# SRC01.net
KiCad netlist of a schematic drawn in EAGLE
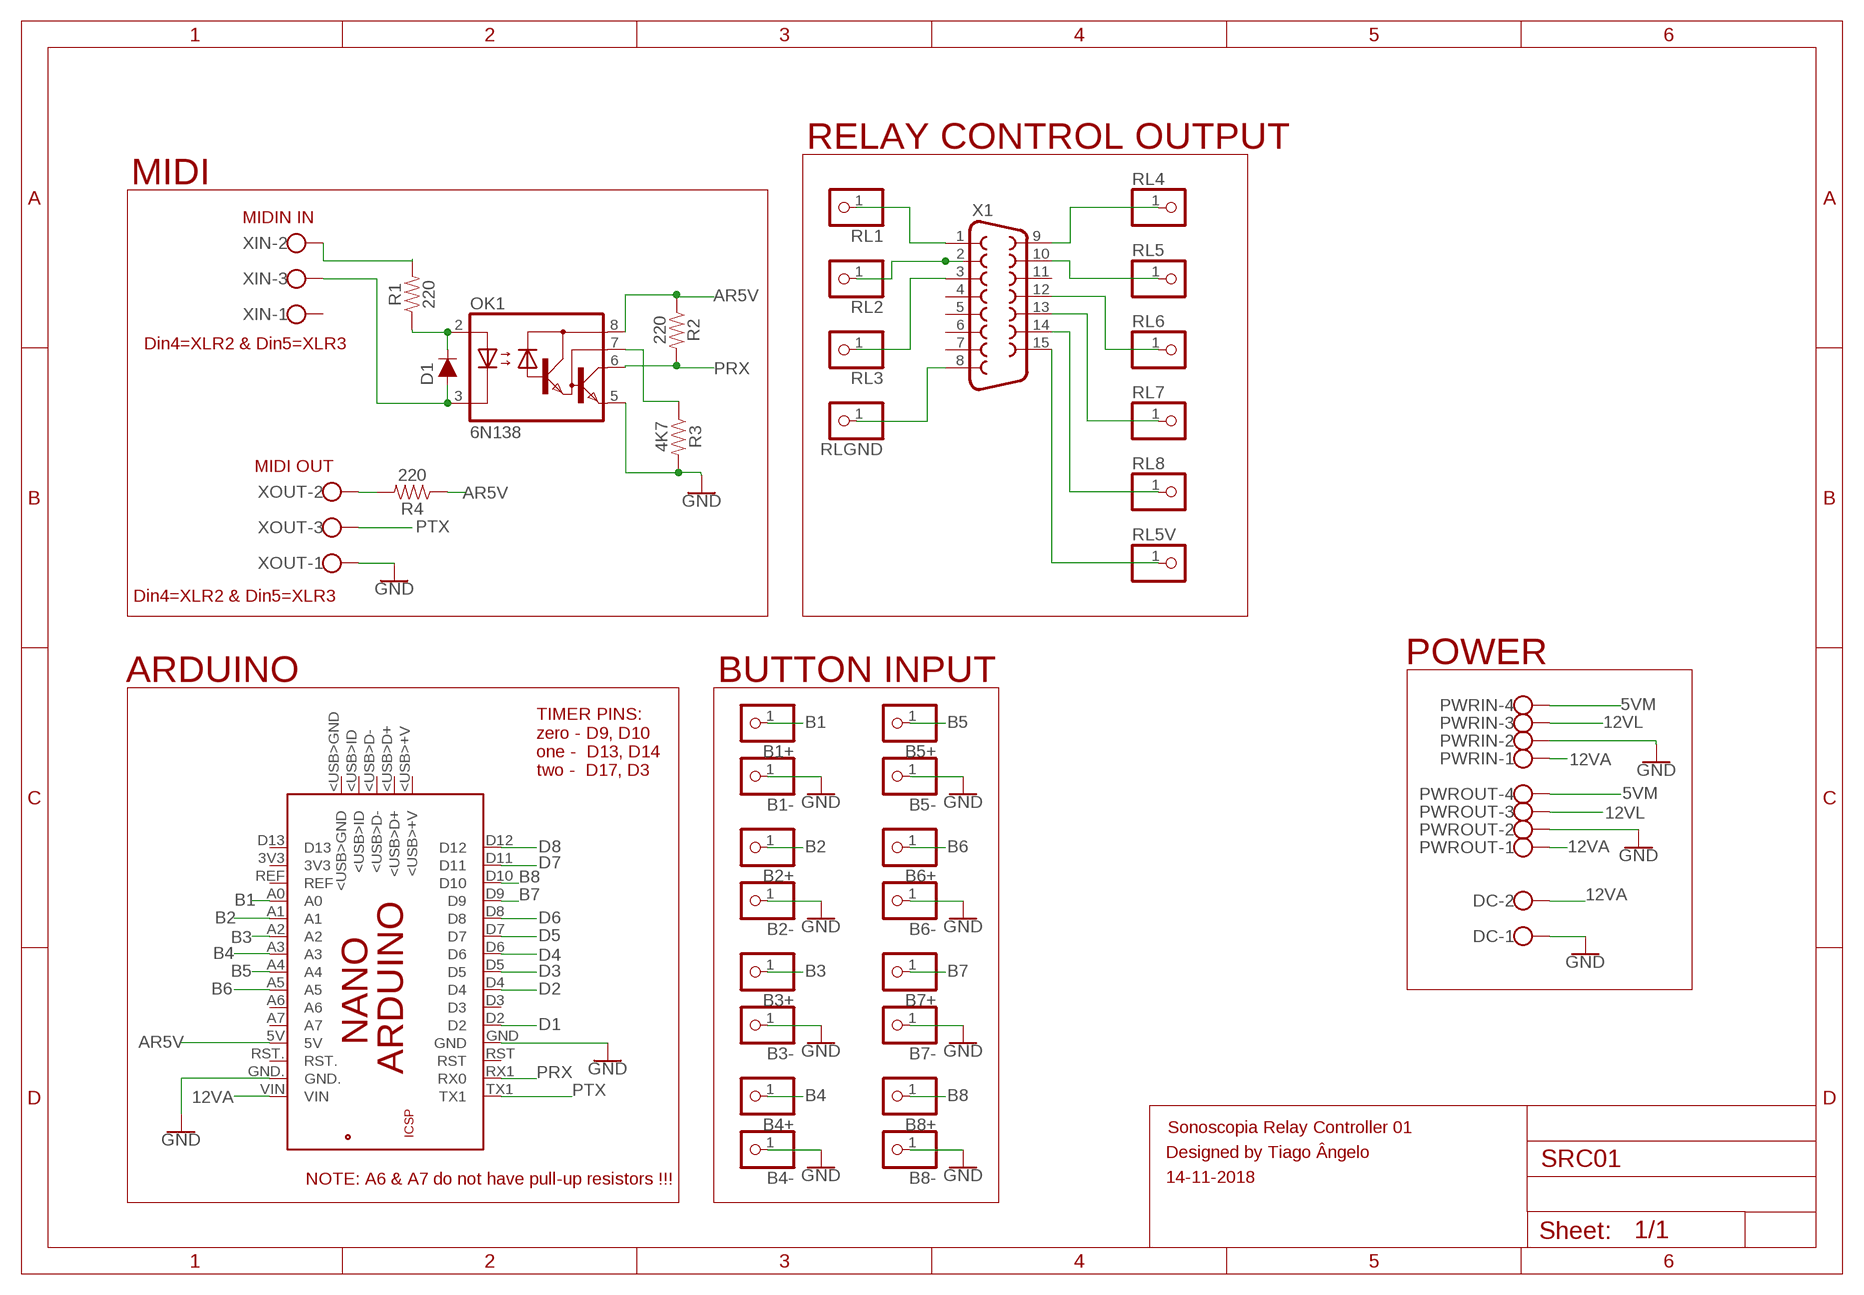
[diagram p0: schematic, sheet 1]

(export (version "E")
  (design (tool "Eeschema 10.0.6"))
  (components
    (comp (ref "B1+")
      (value "PINHD-1X1")
      (footprint "eagle-import:1X01")
      (libsource (lib "eagle-import") (part "PINHD-1X1"))
    )
    (comp (ref "B1-")
      (value "PINHD-1X1")
      (footprint "eagle-import:1X01")
      (libsource (lib "eagle-import") (part "PINHD-1X1"))
    )
    (comp (ref "B2+")
      (value "PINHD-1X1")
      (footprint "eagle-import:1X01")
      (libsource (lib "eagle-import") (part "PINHD-1X1"))
    )
    (comp (ref "B2-")
      (value "PINHD-1X1")
      (footprint "eagle-import:1X01")
      (libsource (lib "eagle-import") (part "PINHD-1X1"))
    )
    (comp (ref "B3+")
      (value "PINHD-1X1")
      (footprint "eagle-import:1X01")
      (libsource (lib "eagle-import") (part "PINHD-1X1"))
    )
    (comp (ref "B3-")
      (value "PINHD-1X1")
      (footprint "eagle-import:1X01")
      (libsource (lib "eagle-import") (part "PINHD-1X1"))
    )
    (comp (ref "B4+")
      (value "PINHD-1X1")
      (footprint "eagle-import:1X01")
      (libsource (lib "eagle-import") (part "PINHD-1X1"))
    )
    (comp (ref "B4-")
      (value "PINHD-1X1")
      (footprint "eagle-import:1X01")
      (libsource (lib "eagle-import") (part "PINHD-1X1"))
    )
    (comp (ref "B5+")
      (value "PINHD-1X1")
      (footprint "eagle-import:1X01")
      (libsource (lib "eagle-import") (part "PINHD-1X1"))
    )
    (comp (ref "B5-")
      (value "PINHD-1X1")
      (footprint "eagle-import:1X01")
      (libsource (lib "eagle-import") (part "PINHD-1X1"))
    )
    (comp (ref "B6+")
      (value "PINHD-1X1")
      (footprint "eagle-import:1X01")
      (libsource (lib "eagle-import") (part "PINHD-1X1"))
    )
    (comp (ref "B6-")
      (value "PINHD-1X1")
      (footprint "eagle-import:1X01")
      (libsource (lib "eagle-import") (part "PINHD-1X1"))
    )
    (comp (ref "B7+")
      (value "PINHD-1X1")
      (footprint "eagle-import:1X01")
      (libsource (lib "eagle-import") (part "PINHD-1X1"))
    )
    (comp (ref "B7-")
      (value "PINHD-1X1")
      (footprint "eagle-import:1X01")
      (libsource (lib "eagle-import") (part "PINHD-1X1"))
    )
    (comp (ref "B8+")
      (value "PINHD-1X1")
      (footprint "eagle-import:1X01")
      (libsource (lib "eagle-import") (part "PINHD-1X1"))
    )
    (comp (ref "B8-")
      (value "PINHD-1X1")
      (footprint "eagle-import:1X01")
      (libsource (lib "eagle-import") (part "PINHD-1X1"))
    )
    (comp (ref "D1")
      (value "200mA/100V/1V")
      (footprint "eagle-import:DIODE-1N4148")
      (libsource (lib "eagle-import") (part "DIODE-1N4148"))
    )
    (comp (ref "DC")
      (value "W237-102")
      (footprint "eagle-import:W237-102")
      (fields (field (name "MPN") "237-102"))
      (libsource (lib "eagle-import") (part "W237-102"))
    )
    (comp (ref "OK1")
      (value "6N138")
      (footprint "eagle-import:DIL08")
      (fields (field (name "MF") "VISHAY/TELEFUNKEN"))
      (libsource (lib "eagle-import") (part "6N138"))
    )
    (comp (ref "PCB1")
      (value "ARDUINO_NANO")
      (footprint "eagle-import:ARDUINO_NANO")
      (libsource (lib "eagle-import") (part "ARDUINO_NANO"))
    )
    (comp (ref "PWRIN")
      (value "W237-4")
      (footprint "eagle-import:W237-4")
      (libsource (lib "eagle-import") (part "W237-4"))
    )
    (comp (ref "PWROUT")
      (value "W237-4")
      (footprint "eagle-import:W237-4")
      (libsource (lib "eagle-import") (part "W237-4"))
    )
    (comp (ref "R1")
      (value "220")
      (footprint "eagle-import:AXIAL-0.3")
      (libsource (lib "eagle-import") (part "1KOHM-HORIZ-1/4W-5%"))
    )
    (comp (ref "R2")
      (value "220")
      (footprint "eagle-import:AXIAL-0.3")
      (libsource (lib "eagle-import") (part "1KOHM-HORIZ-1/4W-5%"))
    )
    (comp (ref "R3")
      (value "4K7")
      (footprint "eagle-import:AXIAL-0.3")
      (libsource (lib "eagle-import") (part "1KOHM-HORIZ-1/4W-5%"))
    )
    (comp (ref "R4")
      (value "220")
      (footprint "eagle-import:AXIAL-0.3")
      (libsource (lib "eagle-import") (part "1KOHM-HORIZ-1/4W-5%"))
    )
    (comp (ref "RL1")
      (value "PINHD-1X1")
      (footprint "eagle-import:1X01")
      (libsource (lib "eagle-import") (part "PINHD-1X1"))
    )
    (comp (ref "RL2")
      (value "PINHD-1X1")
      (footprint "eagle-import:1X01")
      (libsource (lib "eagle-import") (part "PINHD-1X1"))
    )
    (comp (ref "RL3")
      (value "PINHD-1X1")
      (footprint "eagle-import:1X01")
      (libsource (lib "eagle-import") (part "PINHD-1X1"))
    )
    (comp (ref "RL4")
      (value "PINHD-1X1")
      (footprint "eagle-import:1X01")
      (libsource (lib "eagle-import") (part "PINHD-1X1"))
    )
    (comp (ref "RL5")
      (value "PINHD-1X1")
      (footprint "eagle-import:1X01")
      (libsource (lib "eagle-import") (part "PINHD-1X1"))
    )
    (comp (ref "RL5V")
      (value "PINHD-1X1")
      (footprint "eagle-import:1X01")
      (libsource (lib "eagle-import") (part "PINHD-1X1"))
    )
    (comp (ref "RL6")
      (value "PINHD-1X1")
      (footprint "eagle-import:1X01")
      (libsource (lib "eagle-import") (part "PINHD-1X1"))
    )
    (comp (ref "RL7")
      (value "PINHD-1X1")
      (footprint "eagle-import:1X01")
      (libsource (lib "eagle-import") (part "PINHD-1X1"))
    )
    (comp (ref "RL8")
      (value "PINHD-1X1")
      (footprint "eagle-import:1X01")
      (libsource (lib "eagle-import") (part "PINHD-1X1"))
    )
    (comp (ref "RLGND")
      (value "PINHD-1X1")
      (footprint "eagle-import:1X01")
      (libsource (lib "eagle-import") (part "PINHD-1X1"))
    )
    (comp (ref "X1")
      (value "F15HDV")
      (footprint "eagle-import:HDF15V")
      (libsource (lib "eagle-import") (part "F15HDV"))
    )
    (comp (ref "XIN")
      (value "W237-103")
      (footprint "eagle-import:W237-103")
      (fields (field (name "MPN") "237-103"))
      (libsource (lib "eagle-import") (part "W237-103"))
    )
    (comp (ref "XOUT")
      (value "W237-103")
      (footprint "eagle-import:W237-103")
      (fields (field (name "MPN") "237-103"))
      (libsource (lib "eagle-import") (part "W237-103"))
    )
  )
  (nets
    (net (code "1") (name "/5VM") (class "Default")
      (node (ref "PWRIN") (pin "4") (pinfunction "KL_4") (pintype "passive"))
      (node (ref "PWROUT") (pin "4") (pinfunction "KL_4") (pintype "passive"))
    )
    (net (code "2") (name "/12VA") (class "Default")
      (node (ref "DC") (pin "2") (pinfunction "KL_2") (pintype "passive"))
      (node (ref "PCB1") (pin "VIN") (pinfunction "VIN_VIN") (pintype "bidirectional"))
      (node (ref "PWRIN") (pin "1") (pinfunction "KL_1") (pintype "passive"))
      (node (ref "PWROUT") (pin "1") (pinfunction "KL_1") (pintype "passive"))
    )
    (net (code "3") (name "/12VL") (class "Default")
      (node (ref "PWRIN") (pin "3") (pinfunction "KL_3") (pintype "passive"))
      (node (ref "PWROUT") (pin "3") (pinfunction "KL_3") (pintype "passive"))
    )
    (net (code "4") (name "/AR5V") (class "Default")
      (node (ref "OK1") (pin "8") (pinfunction "VCC_8") (pintype "passive"))
      (node (ref "PCB1") (pin "5V") (pinfunction "5V_5V") (pintype "bidirectional"))
      (node (ref "R2") (pin "P$1") (pinfunction "1_P$1") (pintype "passive"))
      (node (ref "R4") (pin "P$1") (pinfunction "1_P$1") (pintype "passive"))
    )
    (net (code "5") (name "/B1") (class "Default")
      (node (ref "B1+") (pin "1") (pinfunction "1_1") (pintype "passive"))
      (node (ref "PCB1") (pin "A0") (pinfunction "A0_A0") (pintype "bidirectional"))
    )
    (net (code "6") (name "/B2") (class "Default")
      (node (ref "B2+") (pin "1") (pinfunction "1_1") (pintype "passive"))
      (node (ref "PCB1") (pin "A1") (pinfunction "A1_A1") (pintype "bidirectional"))
    )
    (net (code "7") (name "/B3") (class "Default")
      (node (ref "B3+") (pin "1") (pinfunction "1_1") (pintype "passive"))
      (node (ref "PCB1") (pin "A2") (pinfunction "A2_A2") (pintype "bidirectional"))
    )
    (net (code "8") (name "/B4") (class "Default")
      (node (ref "B4+") (pin "1") (pinfunction "1_1") (pintype "passive"))
      (node (ref "PCB1") (pin "A3") (pinfunction "A3_A3") (pintype "bidirectional"))
    )
    (net (code "9") (name "/B5") (class "Default")
      (node (ref "B5+") (pin "1") (pinfunction "1_1") (pintype "passive"))
      (node (ref "PCB1") (pin "A4") (pinfunction "A4_A4") (pintype "bidirectional"))
    )
    (net (code "10") (name "/B6") (class "Default")
      (node (ref "B6+") (pin "1") (pinfunction "1_1") (pintype "passive"))
      (node (ref "PCB1") (pin "A5") (pinfunction "A5_A5") (pintype "bidirectional"))
    )
    (net (code "11") (name "/B7") (class "Default")
      (node (ref "B7+") (pin "1") (pinfunction "1_1") (pintype "passive"))
      (node (ref "PCB1") (pin "D9") (pinfunction "D9_D9") (pintype "bidirectional"))
    )
    (net (code "12") (name "/B8") (class "Default")
      (node (ref "B8+") (pin "1") (pinfunction "1_1") (pintype "passive"))
      (node (ref "PCB1") (pin "D10") (pinfunction "D10_D10") (pintype "bidirectional"))
    )
    (net (code "13") (name "/D1") (class "Default")
      (node (ref "PCB1") (pin "D2") (pinfunction "D2_D2") (pintype "bidirectional"))
    )
    (net (code "14") (name "/D2") (class "Default")
      (node (ref "PCB1") (pin "D4") (pinfunction "D4_D4") (pintype "bidirectional"))
    )
    (net (code "15") (name "/D3") (class "Default")
      (node (ref "PCB1") (pin "D5") (pinfunction "D5_D5") (pintype "bidirectional"))
      (node (ref "RL3") (pin "1") (pinfunction "1_1") (pintype "passive"))
      (node (ref "X1") (pin "3") (pinfunction "3_3") (pintype "passive"))
    )
    (net (code "16") (name "/D4") (class "Default")
      (node (ref "PCB1") (pin "D6") (pinfunction "D6_D6") (pintype "bidirectional"))
    )
    (net (code "17") (name "/D5") (class "Default")
      (node (ref "PCB1") (pin "D7") (pinfunction "D7_D7") (pintype "bidirectional"))
    )
    (net (code "18") (name "/D6") (class "Default")
      (node (ref "PCB1") (pin "D8") (pinfunction "D8_D8") (pintype "bidirectional"))
    )
    (net (code "19") (name "/D7") (class "Default")
      (node (ref "PCB1") (pin "D11") (pinfunction "D11_D11") (pintype "bidirectional"))
    )
    (net (code "20") (name "/D8") (class "Default")
      (node (ref "PCB1") (pin "D12") (pinfunction "D12_D12") (pintype "bidirectional"))
    )
    (net (code "21") (name "/PRX") (class "Default")
      (node (ref "OK1") (pin "6") (pinfunction "VO_6") (pintype "passive"))
      (node (ref "PCB1") (pin "RX1") (pinfunction "RX0_RX1") (pintype "bidirectional"))
      (node (ref "R2") (pin "P$2") (pinfunction "2_P$2") (pintype "passive"))
    )
    (net (code "22") (name "/PTX") (class "Default")
      (node (ref "PCB1") (pin "TX1") (pinfunction "TX1_TX1") (pintype "bidirectional"))
      (node (ref "XOUT") (pin "3") (pinfunction "KL_3") (pintype "passive"))
    )
    (net (code "23") (name "GND") (class "Default")
      (node (ref "B1-") (pin "1") (pinfunction "1_1") (pintype "passive"))
      (node (ref "B2-") (pin "1") (pinfunction "1_1") (pintype "passive"))
      (node (ref "B3-") (pin "1") (pinfunction "1_1") (pintype "passive"))
      (node (ref "B4-") (pin "1") (pinfunction "1_1") (pintype "passive"))
      (node (ref "B5-") (pin "1") (pinfunction "1_1") (pintype "passive"))
      (node (ref "B6-") (pin "1") (pinfunction "1_1") (pintype "passive"))
      (node (ref "B7-") (pin "1") (pinfunction "1_1") (pintype "passive"))
      (node (ref "B8-") (pin "1") (pinfunction "1_1") (pintype "passive"))
      (node (ref "DC") (pin "1") (pinfunction "KL_1") (pintype "passive"))
      (node (ref "OK1") (pin "5") (pinfunction "GND_5") (pintype "passive"))
      (node (ref "PCB1") (pin "GND") (pinfunction "GND_GND") (pintype "bidirectional"))
      (node (ref "PCB1") (pin "GND.") (pinfunction "GND._GND.") (pintype "bidirectional"))
      (node (ref "PWRIN") (pin "2") (pinfunction "KL_2") (pintype "passive"))
      (node (ref "PWROUT") (pin "2") (pinfunction "KL_2") (pintype "passive"))
      (node (ref "R3") (pin "P$2") (pinfunction "2_P$2") (pintype "passive"))
      (node (ref "XOUT") (pin "1") (pinfunction "KL_1") (pintype "passive"))
    )
    (net (code "24") (name "Net-(OK1-A)") (class "Default")
      (node (ref "D1") (pin "C") (pinfunction "C_C") (pintype "passive"))
      (node (ref "OK1") (pin "2") (pinfunction "A_2") (pintype "passive"))
      (node (ref "R1") (pin "P$1") (pinfunction "1_P$1") (pintype "passive"))
    )
    (net (code "25") (name "Net-(OK1-C)") (class "Default")
      (node (ref "D1") (pin "A") (pinfunction "A_A") (pintype "passive"))
      (node (ref "OK1") (pin "3") (pinfunction "C_3") (pintype "passive"))
      (node (ref "XIN") (pin "3") (pinfunction "KL_3") (pintype "passive"))
    )
    (net (code "26") (name "Net-(OK1-VB)") (class "Default")
      (node (ref "OK1") (pin "7") (pinfunction "VB_7") (pintype "passive"))
      (node (ref "R3") (pin "P$1") (pinfunction "1_P$1") (pintype "passive"))
    )
    (net (code "27") (name "Net-(R1-2)") (class "Default")
      (node (ref "R1") (pin "P$2") (pinfunction "2_P$2") (pintype "passive"))
      (node (ref "XIN") (pin "2") (pinfunction "KL_2") (pintype "passive"))
    )
    (net (code "28") (name "Net-(R4-2)") (class "Default")
      (node (ref "R4") (pin "P$2") (pinfunction "2_P$2") (pintype "passive"))
      (node (ref "XOUT") (pin "2") (pinfunction "KL_2") (pintype "passive"))
    )
    (net (code "29") (name "Net-(RL1-Pad1)") (class "Default")
      (node (ref "RL1") (pin "1") (pinfunction "1_1") (pintype "passive"))
      (node (ref "X1") (pin "1") (pinfunction "1_1") (pintype "passive"))
    )
    (net (code "30") (name "Net-(RL2-Pad1)") (class "Default")
      (node (ref "RL2") (pin "1") (pinfunction "1_1") (pintype "passive"))
      (node (ref "X1") (pin "2") (pinfunction "2_2") (pintype "passive"))
    )
    (net (code "31") (name "Net-(RL4-Pad1)") (class "Default")
      (node (ref "RL4") (pin "1") (pinfunction "1_1") (pintype "passive"))
      (node (ref "X1") (pin "9") (pinfunction "9_9") (pintype "passive"))
    )
    (net (code "32") (name "Net-(RL5-Pad1)") (class "Default")
      (node (ref "RL5") (pin "1") (pinfunction "1_1") (pintype "passive"))
      (node (ref "X1") (pin "10") (pinfunction "10_10") (pintype "passive"))
    )
    (net (code "33") (name "Net-(RL5V-Pad1)") (class "Default")
      (node (ref "RL5V") (pin "1") (pinfunction "1_1") (pintype "passive"))
      (node (ref "X1") (pin "15") (pinfunction "15_15") (pintype "passive"))
    )
    (net (code "34") (name "Net-(RL6-Pad1)") (class "Default")
      (node (ref "RL6") (pin "1") (pinfunction "1_1") (pintype "passive"))
      (node (ref "X1") (pin "12") (pinfunction "12_12") (pintype "passive"))
    )
    (net (code "35") (name "Net-(RL7-Pad1)") (class "Default")
      (node (ref "RL7") (pin "1") (pinfunction "1_1") (pintype "passive"))
      (node (ref "X1") (pin "13") (pinfunction "13_13") (pintype "passive"))
    )
    (net (code "36") (name "Net-(RL8-Pad1)") (class "Default")
      (node (ref "RL8") (pin "1") (pinfunction "1_1") (pintype "passive"))
      (node (ref "X1") (pin "14") (pinfunction "14_14") (pintype "passive"))
    )
    (net (code "37") (name "Net-(RLGND-Pad1)") (class "Default")
      (node (ref "RLGND") (pin "1") (pinfunction "1_1") (pintype "passive"))
      (node (ref "X1") (pin "8") (pinfunction "8_8") (pintype "passive"))
    )
    (net (code "38") (name "unconnected-(PCB1-Pad3V3)") (class "Default")
      (node (ref "PCB1") (pin "3V3") (pinfunction "3V3_3V3") (pintype "bidirectional"))
    )
    (net (code "39") (name "unconnected-(PCB1-Pad5V.)") (class "Default")
      (node (ref "PCB1") (pin "5V.") (pinfunction "5V._5V.") (pintype "bidirectional"))
    )
    (net (code "40") (name "unconnected-(PCB1-Pad<USB>+V)") (class "Default")
      (node (ref "PCB1") (pin "<USB>+V") (pinfunction "<USB>+V_<USB>+V") (pintype "bidirectional"))
    )
    (net (code "41") (name "unconnected-(PCB1-Pad<USB>D+)") (class "Default")
      (node (ref "PCB1") (pin "<USB>D+") (pinfunction "<USB>D+_<USB>D+") (pintype "bidirectional"))
    )
    (net (code "42") (name "unconnected-(PCB1-Pad<USB>D-)") (class "Default")
      (node (ref "PCB1") (pin "<USB>D-") (pinfunction "<USB>D-_<USB>D-") (pintype "bidirectional"))
    )
    (net (code "43") (name "unconnected-(PCB1-Pad<USB>GND)") (class "Default")
      (node (ref "PCB1") (pin "<USB>GND") (pinfunction "<USB>GND_<USB>GND") (pintype "bidirectional"))
    )
    (net (code "44") (name "unconnected-(PCB1-Pad<USB>ID)") (class "Default")
      (node (ref "PCB1") (pin "<USB>ID") (pinfunction "<USB>ID_<USB>ID") (pintype "bidirectional"))
    )
    (net (code "45") (name "unconnected-(PCB1-PadA6)") (class "Default")
      (node (ref "PCB1") (pin "A6") (pinfunction "A6_A6") (pintype "bidirectional"))
    )
    (net (code "46") (name "unconnected-(PCB1-PadA7)") (class "Default")
      (node (ref "PCB1") (pin "A7") (pinfunction "A7_A7") (pintype "bidirectional"))
    )
    (net (code "47") (name "unconnected-(PCB1-PadD3)") (class "Default")
      (node (ref "PCB1") (pin "D3") (pinfunction "D3_D3") (pintype "bidirectional"))
    )
    (net (code "48") (name "unconnected-(PCB1-PadD13)") (class "Default")
      (node (ref "PCB1") (pin "D13") (pinfunction "D13_D13") (pintype "bidirectional"))
    )
    (net (code "49") (name "unconnected-(PCB1-PadGND_)") (class "Default")
      (node (ref "PCB1") (pin "GND_") (pinfunction "GND__GND_") (pintype "bidirectional"))
    )
    (net (code "50") (name "unconnected-(PCB1-PadMISO)") (class "Default")
      (node (ref "PCB1") (pin "MISO") (pinfunction "MISO_MISO") (pintype "bidirectional"))
    )
    (net (code "51") (name "unconnected-(PCB1-PadMOSI)") (class "Default")
      (node (ref "PCB1") (pin "MOSI") (pinfunction "MOSI_MOSI") (pintype "bidirectional"))
    )
    (net (code "52") (name "unconnected-(PCB1-PadREF)") (class "Default")
      (node (ref "PCB1") (pin "REF") (pinfunction "REF_REF") (pintype "bidirectional"))
    )
    (net (code "53") (name "unconnected-(PCB1-PadRESET..)") (class "Default")
      (node (ref "PCB1") (pin "RESET..") (pinfunction "RESET.._RESET..") (pintype "bidirectional"))
    )
    (net (code "54") (name "unconnected-(PCB1-PadRST)") (class "Default")
      (node (ref "PCB1") (pin "RST") (pinfunction "RST_RST") (pintype "bidirectional"))
    )
    (net (code "55") (name "unconnected-(PCB1-PadRST.)") (class "Default")
      (node (ref "PCB1") (pin "RST.") (pinfunction "RST._RST.") (pintype "bidirectional"))
    )
    (net (code "56") (name "unconnected-(PCB1-PadSCK)") (class "Default")
      (node (ref "PCB1") (pin "SCK") (pinfunction "SCK_SCK") (pintype "bidirectional"))
    )
    (net (code "57") (name "unconnected-(X1-Pad4)") (class "Default")
      (node (ref "X1") (pin "4") (pinfunction "4_4") (pintype "passive"))
    )
    (net (code "58") (name "unconnected-(X1-Pad5)") (class "Default")
      (node (ref "X1") (pin "5") (pinfunction "5_5") (pintype "passive"))
    )
    (net (code "59") (name "unconnected-(X1-Pad6)") (class "Default")
      (node (ref "X1") (pin "6") (pinfunction "6_6") (pintype "passive"))
    )
    (net (code "60") (name "unconnected-(X1-Pad7)") (class "Default")
      (node (ref "X1") (pin "7") (pinfunction "7_7") (pintype "passive"))
    )
    (net (code "61") (name "unconnected-(X1-Pad11)") (class "Default")
      (node (ref "X1") (pin "11") (pinfunction "11_11") (pintype "passive"))
    )
    (net (code "62") (name "unconnected-(XINA-KL-Pad1)") (class "Default")
      (node (ref "XIN") (pin "1") (pinfunction "KL_1") (pintype "passive"))
    )
  )
)
